# QUTMS-TSAL2-S01.net
KiCad netlist of a schematic drawn in Altium Designer
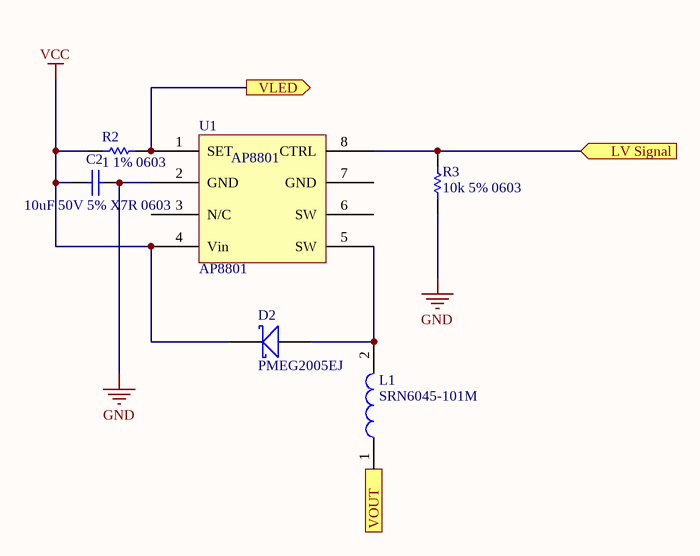
[diagram p0: QUTMS-TSAL2-S01.SchDoc]

(export (version "E")
  (design (tool "Eeschema 10.0.6"))
  (components
    (comp (ref "C2")
      (value "10uF 50V 5% X7R 0603")
      (footprint "Cap_Ceramic_0603(10uf)")
      (description "Capacitor, Ceramic, SMD, 10uF, 50V, 5%, X7R, 0603")
      (libsource (lib "TSALdrive") (part "10uF 50V 5% X7R 0603"))
    )
    (comp (ref "D2")
      (value "PMEG2005EJ")
      (footprint "SOD-323F(shottkey)")
      (description "Diode, Schottky, SMD, 20 V, 500 mA, Single, SOD-323F, 2 Pins, 390 mV")
      (libsource (lib "TSALdrive") (part "PMEG2005EJ"))
    )
    (comp (ref "L1")
      (value "SRN6045-101M")
      (footprint "Bourns Inductor 6x6x4.5mm(100mH)")
      (description "Inductor, 100 µH, 700 mA, Semishielded, 800 mA, SRN6045 Series, 6mm x 6mm x 4.5mm")
      (libsource (lib "TSALdrive") (part "SRN6045-101M"))
    )
    (comp (ref "R2")
      (value "1 1% 0603")
      (footprint "Res_ThinFilm_0603 (1,10k)")
      (description "Resistor, SMD, 1, 0.1W, 1%, 0603")
      (libsource (lib "TSALdrive") (part "1 1% 0603"))
    )
    (comp (ref "R3")
      (value "10k 5% 0603")
      (footprint "Res_ThinFilm_0603 (1,10k)")
      (description "Resistor, SMD, 10k, 0.1W, 5%, 0603")
      (libsource (lib "TSALdrive") (part "10k 5% 0603"))
    )
    (comp (ref "U1")
      (value "AP8801")
      (footprint "SOP8/SO8(AP8801)")
      (description "the LED drver fotr the red and green LED's")
      (libsource (lib "TSALdrive") (part "AP8801"))
    )
  )
  (nets
    (net (code "1") (name "/LV Signal") (class "Default")
      (node (ref "R3") (pin "2") (pinfunction "2_2") (pintype "passive"))
      (node (ref "U1") (pin "8") (pinfunction "CTRL_8") (pintype "passive"))
    )
    (net (code "2") (name "/VLED") (class "Default")
      (node (ref "R2") (pin "2") (pinfunction "2_2") (pintype "passive"))
      (node (ref "U1") (pin "1") (pinfunction "SET_1") (pintype "passive"))
    )
    (net (code "3") (name "/VOUT") (class "Default")
      (node (ref "L1") (pin "1") (pinfunction "1_1") (pintype "passive"))
    )
    (net (code "4") (name "GND") (class "Default")
      (node (ref "C2") (pin "2") (pinfunction "2_2") (pintype "passive"))
      (node (ref "R3") (pin "1") (pinfunction "1_1") (pintype "passive"))
      (node (ref "U1") (pin "2") (pinfunction "GND_2") (pintype "passive"))
    )
    (net (code "5") (name "Net-(D2-Anode)") (class "Default")
      (node (ref "D2") (pin "A") (pinfunction "Anode_A") (pintype "passive"))
      (node (ref "L1") (pin "2") (pinfunction "2_2") (pintype "passive"))
      (node (ref "U1") (pin "5") (pinfunction "SW_5") (pintype "passive"))
    )
    (net (code "6") (name "VCC") (class "Default")
      (node (ref "C2") (pin "1") (pinfunction "1_1") (pintype "passive"))
      (node (ref "D2") (pin "K") (pinfunction "Cathode_K") (pintype "passive"))
      (node (ref "R2") (pin "1") (pinfunction "1_1") (pintype "passive"))
      (node (ref "U1") (pin "4") (pinfunction "Vin_4") (pintype "passive"))
    )
    (net (code "7") (name "unconnected-(U1-GND-Pad7)") (class "Default")
      (node (ref "U1") (pin "7") (pinfunction "GND_7") (pintype "passive"))
    )
    (net (code "8") (name "unconnected-(U1-N{slash}C-Pad3)") (class "Default")
      (node (ref "U1") (pin "3") (pinfunction "N/C_3") (pintype "passive"))
    )
    (net (code "9") (name "unconnected-(U1-SW-Pad6)") (class "Default")
      (node (ref "U1") (pin "6") (pinfunction "SW_6") (pintype "passive"))
    )
  )
)
